# W5500_HR911105A.net
KiCad netlist of a schematic drawn in Altium Designer
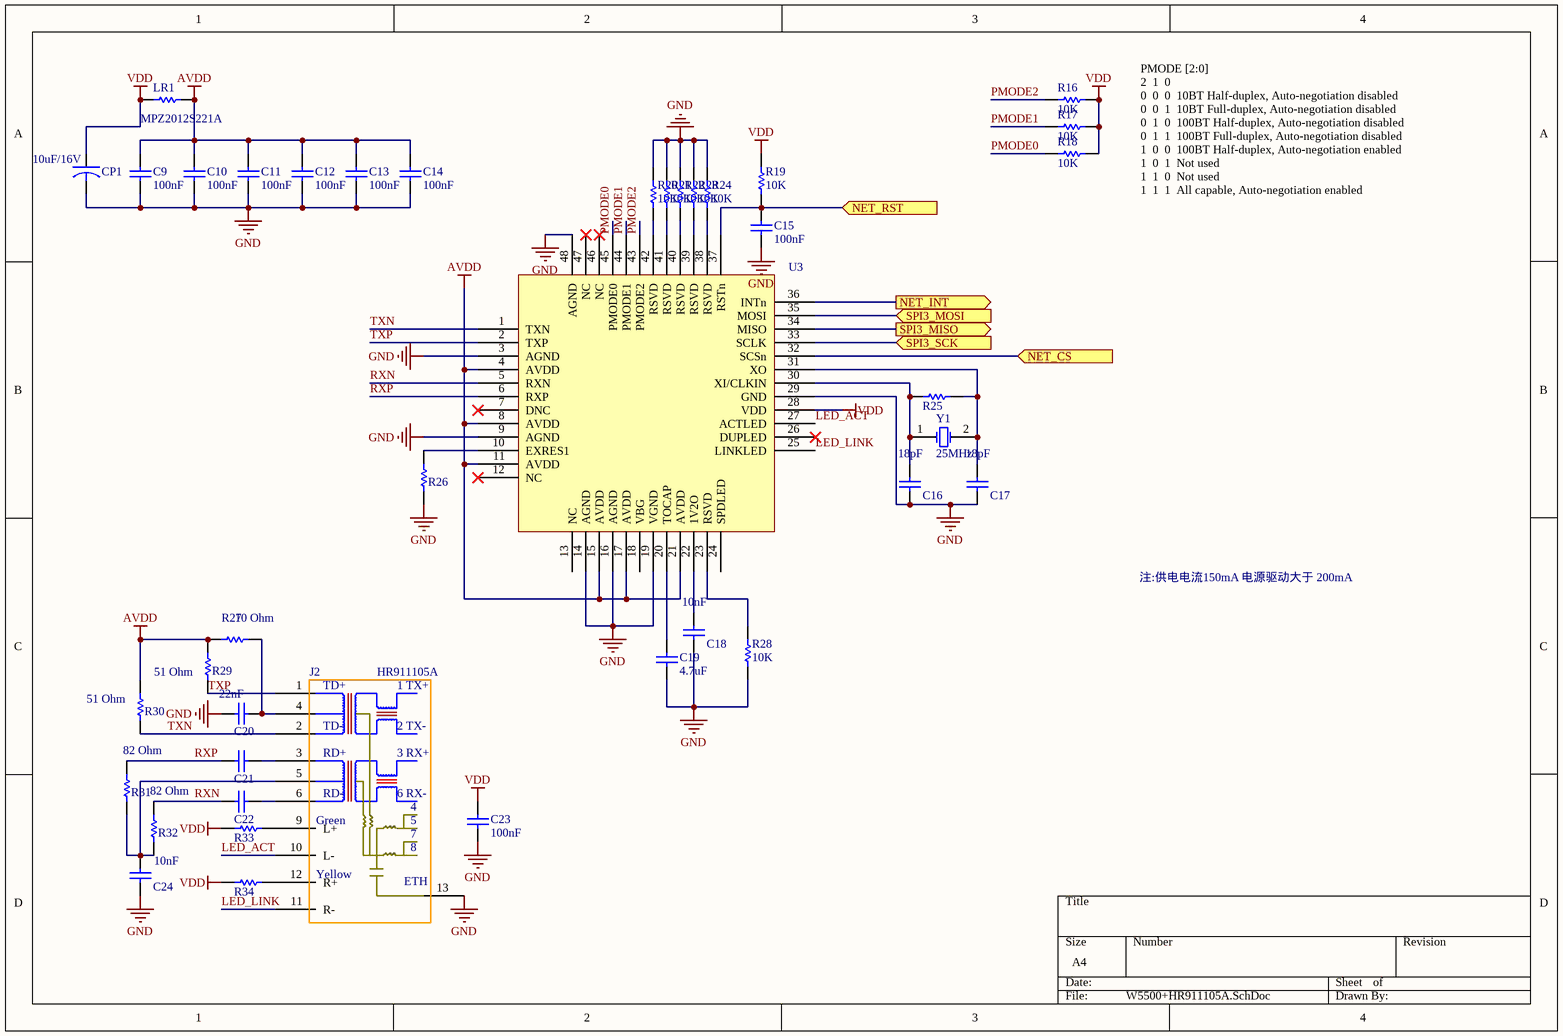
[diagram p0: W5500+HR911105A.SchDoc]

(export (version "E")
  (design (tool "Eeschema 10.0.6"))
  (components
    (comp (ref "C9")
      (value "100nF")
      (footprint "2012[0805]06CD")
      (description "CAP 100nF 50V ±5% 0805 (2012 Metric) Thickness 1mm SMD")
      (fields (field (name "TOLERANCE") "±5%") (field (name "Comment") "CAP 100nF 50V 0805(2012)"))
      (libsource (lib "Altium Content Vault") (part "CMP-1036-04418-1"))
    )
    (comp (ref "C10")
      (value "100nF")
      (footprint "2012[0805]06CD")
      (description "CAP 100nF 50V ±5% 0805 (2012 Metric) Thickness 1mm SMD")
      (fields (field (name "TOLERANCE") "±5%") (field (name "Comment") "CAP 100nF 50V 0805(2012)"))
      (libsource (lib "Altium Content Vault") (part "CMP-1036-04418-1"))
    )
    (comp (ref "C11")
      (value "100nF")
      (footprint "2012[0805]06CD")
      (description "CAP 100nF 50V ±5% 0805 (2012 Metric) Thickness 1mm SMD")
      (fields (field (name "TOLERANCE") "±5%") (field (name "Comment") "CAP 100nF 50V 0805(2012)"))
      (libsource (lib "Altium Content Vault") (part "CMP-1036-04418-1"))
    )
    (comp (ref "C12")
      (value "100nF")
      (footprint "2012[0805]06CD")
      (description "CAP 100nF 50V ±5% 0805 (2012 Metric) Thickness 1mm SMD")
      (fields (field (name "TOLERANCE") "±5%") (field (name "Comment") "CAP 100nF 50V 0805(2012)"))
      (libsource (lib "Altium Content Vault") (part "CMP-1036-04418-1"))
    )
    (comp (ref "C13")
      (value "100nF")
      (footprint "2012[0805]06CD")
      (description "CAP 100nF 50V ±5% 0805 (2012 Metric) Thickness 1mm SMD")
      (fields (field (name "TOLERANCE") "±5%") (field (name "Comment") "CAP 100nF 50V 0805(2012)"))
      (libsource (lib "Altium Content Vault") (part "CMP-1036-04418-1"))
    )
    (comp (ref "C14")
      (value "100nF")
      (footprint "2012[0805]06CD")
      (description "CAP 100nF 50V ±5% 0805 (2012 Metric) Thickness 1mm SMD")
      (fields (field (name "TOLERANCE") "±5%") (field (name "Comment") "CAP 100nF 50V 0805(2012)"))
      (libsource (lib "Altium Content Vault") (part "CMP-1036-04418-1"))
    )
    (comp (ref "C15")
      (value "100nF")
      (footprint "2012[0805]06CD")
      (description "CAP 100nF 50V ±5% 0805 (2012 Metric) Thickness 1.45mm SMD")
      (fields (field (name "TOLERANCE") "±5%") (field (name "Comment") "CAP 100nF 50V 0805(2012)"))
      (libsource (lib "Altium Content Vault") (part "CMP-1036-04417-1"))
    )
    (comp (ref "C16")
      (value "18pF")
      (footprint "2012[0805]100_L")
      (description "CAP 18pF 50V ±1% 0805 (2012 Metric) Thickness 0.75mm SMD")
      (fields (field (name "TOLERANCE") "±1%") (field (name "Comment") "CAP 18pF 50V 0805(2012)"))
      (libsource (lib "Altium Content Vault") (part "CMP-1036-01136-1"))
    )
    (comp (ref "C17")
      (value "18pF")
      (footprint "2012[0805]100_L")
      (description "CAP 18pF 50V ±1% 0805 (2012 Metric) Thickness 0.75mm SMD")
      (fields (field (name "TOLERANCE") "±1%") (field (name "Comment") "CAP 18pF 50V 0805(2012)"))
      (libsource (lib "Altium Content Vault") (part "CMP-1036-01136-1"))
    )
    (comp (ref "C18")
      (value "10nF")
      (footprint "2012[0805]100_L")
      (description "CAP 10nF 50V ±1% 0805 (2012 Metric) Thickness 1mm SMD")
      (fields (field (name "TOLERANCE") "±1%") (field (name "Comment") "CAP 10nF 50V 0805(2012)"))
      (libsource (lib "Altium Content Vault") (part "CMP-1036-03837-1"))
    )
    (comp (ref "C19")
      (value "4.7uF")
      (footprint "2012[0805]13CD")
      (description "CAP 4.7uF 50V ±10% 0805 (2012 Metric) Thickness 1.45mm SMD")
      (fields (field (name "TOLERANCE") "±10%") (field (name "Comment") "CAP 4.7uF 50V 0805(2012)"))
      (libsource (lib "Altium Content Vault") (part "CMP-1036-04900-1"))
    )
    (comp (ref "C20")
      (value "22nF")
      (footprint "2012[0805]100_L")
      (description "CAP 22nF 50V ±5% 0805 (2012 Metric) Thickness 1.2mm SMD")
      (fields (field (name "TOLERANCE") "±5%") (field (name "Comment") "CAP 22nF 50V 0805(2012)"))
      (libsource (lib "Altium Content Vault") (part "CMP-1036-04061-1"))
    )
    (comp (ref "C21")
      (value "CAP 6.8nF 50V 0805(2012)")
      (footprint "2012[0805]100_L")
      (description "CAP 6.8nF 50V ±1% 0805 (2012 Metric) Thickness 1mm SMD")
      (fields (field (name "TOLERANCE") "±1%"))
      (libsource (lib "Altium Content Vault") (part "CAP"))
    )
    (comp (ref "C22")
      (value "CAP 6.8nF 50V 0805(2012)")
      (footprint "2012[0805]100_L")
      (description "CAP 6.8nF 50V ±1% 0805 (2012 Metric) Thickness 1mm SMD")
      (fields (field (name "TOLERANCE") "±1%"))
      (libsource (lib "Altium Content Vault") (part "CAP"))
    )
    (comp (ref "C23")
      (value "100nF")
      (footprint "2012[0805]06CD")
      (description "CAP 100nF 50V ±5% 0805 (2012 Metric) Thickness 1mm SMD")
      (fields (field (name "TOLERANCE") "±5%") (field (name "Comment") "CAP 100nF 50V 0805(2012)"))
      (libsource (lib "Altium Content Vault") (part "CMP-1036-04418-1"))
    )
    (comp (ref "C24")
      (value "10nF")
      (footprint "2012[0805]100_L")
      (description "CAP 10nF 50V ±1% 0805 (2012 Metric) Thickness 1mm SMD")
      (fields (field (name "TOLERANCE") "±1%") (field (name "Comment") "CAP 10nF 50V 0805(2012)"))
      (libsource (lib "Altium Content Vault") (part "CMP-1036-03837-1"))
    )
    (comp (ref "CP1")
      (value "10uF/16V")
      (footprint "3216[1206]CB")
      (description "钽质电容器-固体SMD 16volts 10uF 10%")
      (fields (field (name "MANUFACTURER") "AVX") (field (name "MANUFACTURER PART NUMBER") "TAJA106K016RNJ"))
      (libsource (lib "*") (part "CAPACITOR"))
    )
    (comp (ref "J2") (value "HR911105A") (footprint "HR911105A") (libsource (lib "*") (part "HR911102")))
    (comp (ref "LR1")
      (value "MPZ2012S221A")
      (footprint "2012[0805]RL")
      (description "电磁干扰滤波珠子、扼流圈和阵列 Ferrite Chip Beads")
      (fields (field (name "MANUFACTURER") "TDK"))
      (libsource (lib "Miscellaneous Devices") (part "Res Semi"))
    )
    (comp (ref "R16")
      (value "10K")
      (footprint "2012[0805]R")
      (description "10K 0.125W 1% 0805 (2012 Metric)  SMD")
      (fields (field (name "TOLERANCE") "1 %") (field (name "POWER") "0.125 W"))
      (libsource (lib "Altium Content Vault") (part "CMP-1013-00623-1"))
    )
    (comp (ref "R17")
      (value "10K")
      (footprint "2012[0805]R")
      (description "10K 0.125W 1% 0805 (2012 Metric)  SMD")
      (fields (field (name "TOLERANCE") "1 %") (field (name "POWER") "0.125 W"))
      (libsource (lib "Altium Content Vault") (part "CMP-1013-00623-1"))
    )
    (comp (ref "R18")
      (value "10K")
      (footprint "2012[0805]R")
      (description "10K 0.125W 1% 0805 (2012 Metric)  SMD")
      (fields (field (name "TOLERANCE") "1 %") (field (name "POWER") "0.125 W"))
      (libsource (lib "Altium Content Vault") (part "CMP-1013-00623-1"))
    )
    (comp (ref "R19")
      (value "10K")
      (footprint "2012[0805]R")
      (description "10K 0.125W 1% 0805 (2012 Metric)  SMD")
      (fields (field (name "TOLERANCE") "1 %") (field (name "POWER") "0.125 W"))
      (libsource (lib "Altium Content Vault") (part "CMP-1013-00623-1"))
    )
    (comp (ref "R20")
      (value "10K")
      (footprint "2012[0805]R")
      (description "10K 0.125W 1% 0805 (2012 Metric)  SMD")
      (fields (field (name "TOLERANCE") "1 %") (field (name "POWER") "0.125 W"))
      (libsource (lib "Altium Content Vault") (part "CMP-1013-00623-1"))
    )
    (comp (ref "R21")
      (value "10K")
      (footprint "2012[0805]R")
      (description "10K 0.125W 1% 0805 (2012 Metric)  SMD")
      (fields (field (name "TOLERANCE") "1 %") (field (name "POWER") "0.125 W"))
      (libsource (lib "Altium Content Vault") (part "CMP-1013-00623-1"))
    )
    (comp (ref "R22")
      (value "10K")
      (footprint "2012[0805]R")
      (description "10K 0.125W 1% 0805 (2012 Metric)  SMD")
      (fields (field (name "TOLERANCE") "1 %") (field (name "POWER") "0.125 W"))
      (libsource (lib "Altium Content Vault") (part "CMP-1013-00623-1"))
    )
    (comp (ref "R23")
      (value "10K")
      (footprint "2012[0805]R")
      (description "10K 0.125W 1% 0805 (2012 Metric)  SMD")
      (fields (field (name "TOLERANCE") "1 %") (field (name "POWER") "0.125 W"))
      (libsource (lib "Altium Content Vault") (part "CMP-1013-00623-1"))
    )
    (comp (ref "R24")
      (value "10K")
      (footprint "2012[0805]R")
      (description "10K 0.125W 1% 0805 (2012 Metric)  SMD")
      (fields (field (name "TOLERANCE") "1 %") (field (name "POWER") "0.125 W"))
      (libsource (lib "Altium Content Vault") (part "CMP-1013-00623-1"))
    )
    (comp (ref "R25")
      (value "1M 1% 0805(2012)")
      (footprint "2012[0805]R")
      (description "1M 0.125W 1% 0805 (2012 Metric)  SMD")
      (fields (field (name "POWER") "0.125 W") (field (name "TOLERANCE") "1 %"))
      (libsource (lib "Altium Content Vault") (part "RES"))
    )
    (comp (ref "R26")
      (value "12K4 1% 0805(2012)")
      (footprint "2012[0805]R")
      (description "12K4 0.125W 1% 0805 (2012 Metric)  SMD")
      (fields (field (name "POWER") "0.125 W") (field (name "TOLERANCE") "1 %"))
      (libsource (lib "Altium Content Vault") (part "CMP-1013-00633-1"))
    )
    (comp (ref "R27")
      (value "10 Ohm")
      (footprint "2012[0805]R")
      (description "10R 0.125W 5% 0805 (2012 Metric)  SMD")
      (fields (field (name "POWER") "0.125 W") (field (name "TOLERANCE") "5 %"))
      (libsource (lib "Altium Content Vault") (part "CMP-1013-00026-1"))
    )
    (comp (ref "R28")
      (value "10K")
      (footprint "2012[0805]R")
      (description "10K 0.125W 1% 0805 (2012 Metric)  SMD")
      (fields (field (name "TOLERANCE") "1 %") (field (name "POWER") "0.125 W"))
      (libsource (lib "Altium Content Vault") (part "CMP-1013-00623-1"))
    )
    (comp (ref "R29")
      (value "51 Ohm")
      (footprint "2012[0805]R")
      (description "51R 0.125W 5% 0805 (2012 Metric)  SMD")
      (fields (field (name "TOLERANCE") "5 %") (field (name "POWER") "0.125 W"))
      (libsource (lib "Altium Content Vault") (part "CMP-1013-00043-1"))
    )
    (comp (ref "R30")
      (value "51 Ohm")
      (footprint "2012[0805]R")
      (description "51R 0.125W 5% 0805 (2012 Metric)  SMD")
      (fields (field (name "TOLERANCE") "5 %") (field (name "POWER") "0.125 W"))
      (libsource (lib "Altium Content Vault") (part "CMP-1013-00043-1"))
    )
    (comp (ref "R31")
      (value "82 Ohm")
      (footprint "2012[0805]R")
      (description "82R 0.125W 5% 0805 (2012 Metric)  SMD")
      (fields (field (name "POWER") "0.125 W") (field (name "TOLERANCE") "5 %"))
      (libsource (lib "Altium Content Vault") (part "CMP-1013-00048-1"))
    )
    (comp (ref "R32")
      (value "82 Ohm")
      (footprint "2012[0805]R")
      (description "82R 0.125W 5% 0805 (2012 Metric)  SMD")
      (fields (field (name "POWER") "0.125 W") (field (name "TOLERANCE") "5 %"))
      (libsource (lib "Altium Content Vault") (part "CMP-1013-00048-1"))
    )
    (comp (ref "R33")
      (value "270R 5% 0805(2012)")
      (footprint "2012[0805]R")
      (description "270R 0.125W 5% 0805 (2012 Metric)  SMD")
      (fields (field (name "POWER") "0.125 W") (field (name "TOLERANCE") "5 %"))
      (libsource (lib "Altium Content Vault") (part "RES"))
    )
    (comp (ref "R34")
      (value "270R 5% 0805(2012)")
      (footprint "2012[0805]R")
      (description "270R 0.125W 5% 0805 (2012 Metric)  SMD")
      (fields (field (name "POWER") "0.125 W") (field (name "TOLERANCE") "5 %"))
      (libsource (lib "Altium Content Vault") (part "RES"))
    )
    (comp (ref "U3")
      (value "W5500")
      (footprint "LQFP48_N")
      (description "以太网")
      (libsource (lib "mylib") (part "W5500"))
    )
    (comp (ref "Y1")
      (value "25MHz")
      (footprint "XTAL_HC-49")
      (description "Crystal Oscillator")
      (fields (field (name "PUBLISHER") "Altium Limited"))
      (libsource (lib "mylib") (part "XTAL"))
    )
  )
  (nets
    (net (code "1") (name "/LED_ACT") (class "Default")
      (node (ref "J2") (pin "10") (pinfunction "L-_10") (pintype "passive"))
      (node (ref "U3") (pin "27") (pinfunction "ACTLED_27") (pintype "passive"))
    )
    (net (code "2") (name "/LED_LINK") (class "Default")
      (node (ref "J2") (pin "11") (pinfunction "R-_11") (pintype "passive"))
      (node (ref "U3") (pin "25") (pinfunction "LINKLED_25") (pintype "passive"))
    )
    (net (code "3") (name "/NET_CS") (class "Default")
      (node (ref "U3") (pin "32") (pinfunction "SCSn_32") (pintype "passive"))
    )
    (net (code "4") (name "/NET_INT") (class "Default")
      (node (ref "U3") (pin "36") (pinfunction "INTn_36") (pintype "passive"))
    )
    (net (code "5") (name "/NET_RST") (class "Default")
      (node (ref "C15") (pin "1") (pinfunction "1_1") (pintype "passive"))
      (node (ref "R19") (pin "2") (pinfunction "2_2") (pintype "passive"))
      (node (ref "U3") (pin "37") (pinfunction "RSTn_37") (pintype "passive"))
    )
    (net (code "6") (name "/PMODE0") (class "Default")
      (node (ref "R18") (pin "2") (pinfunction "2_2") (pintype "passive"))
      (node (ref "U3") (pin "45") (pinfunction "PMODE0_45") (pintype "passive"))
    )
    (net (code "7") (name "/PMODE1") (class "Default")
      (node (ref "R17") (pin "2") (pinfunction "2_2") (pintype "passive"))
      (node (ref "U3") (pin "44") (pinfunction "PMODE1_44") (pintype "passive"))
    )
    (net (code "8") (name "/PMODE2") (class "Default")
      (node (ref "R16") (pin "2") (pinfunction "2_2") (pintype "passive"))
      (node (ref "U3") (pin "43") (pinfunction "PMODE2_43") (pintype "passive"))
    )
    (net (code "9") (name "/RXN") (class "Default")
      (node (ref "C22") (pin "1") (pinfunction "1_1") (pintype "passive"))
      (node (ref "R32") (pin "2") (pinfunction "2_2") (pintype "passive"))
      (node (ref "U3") (pin "5") (pinfunction "RXN_5") (pintype "passive"))
    )
    (net (code "10") (name "/RXP") (class "Default")
      (node (ref "C21") (pin "1") (pinfunction "1_1") (pintype "passive"))
      (node (ref "R31") (pin "2") (pinfunction "2_2") (pintype "passive"))
      (node (ref "U3") (pin "6") (pinfunction "RXP_6") (pintype "passive"))
    )
    (net (code "11") (name "/SPI3_MISO") (class "Default")
      (node (ref "U3") (pin "34") (pinfunction "MISO_34") (pintype "passive"))
    )
    (net (code "12") (name "/SPI3_MOSI") (class "Default")
      (node (ref "U3") (pin "35") (pinfunction "MOSI_35") (pintype "passive"))
    )
    (net (code "13") (name "/SPI3_SCK") (class "Default")
      (node (ref "U3") (pin "33") (pinfunction "SCLK_33") (pintype "passive"))
    )
    (net (code "14") (name "/TXN") (class "Default")
      (node (ref "J2") (pin "2") (pintype "passive"))
      (node (ref "R30") (pin "1") (pinfunction "1_1") (pintype "passive"))
      (node (ref "U3") (pin "1") (pinfunction "TXN_1") (pintype "passive"))
    )
    (net (code "15") (name "/TXP") (class "Default")
      (node (ref "J2") (pin "1") (pintype "passive"))
      (node (ref "R29") (pin "1") (pinfunction "1_1") (pintype "passive"))
      (node (ref "U3") (pin "2") (pinfunction "TXP_2") (pintype "passive"))
    )
    (net (code "16") (name "AVDD") (class "Default")
      (node (ref "C10") (pin "1") (pinfunction "1_1") (pintype "passive"))
      (node (ref "C11") (pin "1") (pinfunction "1_1") (pintype "passive"))
      (node (ref "C12") (pin "1") (pinfunction "1_1") (pintype "passive"))
      (node (ref "C13") (pin "1") (pinfunction "1_1") (pintype "passive"))
      (node (ref "C14") (pin "1") (pinfunction "1_1") (pintype "passive"))
      (node (ref "C9") (pin "1") (pinfunction "1_1") (pintype "passive"))
      (node (ref "LR1") (pin "1") (pinfunction "1_1") (pintype "passive"))
      (node (ref "R27") (pin "2") (pinfunction "2_2") (pintype "passive"))
      (node (ref "R29") (pin "2") (pinfunction "2_2") (pintype "passive"))
      (node (ref "R30") (pin "2") (pinfunction "2_2") (pintype "passive"))
      (node (ref "U3") (pin "11") (pinfunction "AVDD_11") (pintype "passive"))
      (node (ref "U3") (pin "15") (pinfunction "AVDD_15") (pintype "passive"))
      (node (ref "U3") (pin "17") (pinfunction "AVDD_17") (pintype "passive"))
      (node (ref "U3") (pin "21") (pinfunction "AVDD_21") (pintype "passive"))
      (node (ref "U3") (pin "4") (pinfunction "AVDD_4") (pintype "passive"))
      (node (ref "U3") (pin "8") (pinfunction "AVDD_8") (pintype "passive"))
    )
    (net (code "17") (name "GND") (class "Default")
      (node (ref "C10") (pin "2") (pinfunction "2_2") (pintype "passive"))
      (node (ref "C11") (pin "2") (pinfunction "2_2") (pintype "passive"))
      (node (ref "C12") (pin "2") (pinfunction "2_2") (pintype "passive"))
      (node (ref "C13") (pin "2") (pinfunction "2_2") (pintype "passive"))
      (node (ref "C14") (pin "2") (pinfunction "2_2") (pintype "passive"))
      (node (ref "C15") (pin "2") (pinfunction "2_2") (pintype "passive"))
      (node (ref "C16") (pin "1") (pinfunction "1_1") (pintype "passive"))
      (node (ref "C17") (pin "1") (pinfunction "1_1") (pintype "passive"))
      (node (ref "C18") (pin "1") (pinfunction "1_1") (pintype "passive"))
      (node (ref "C19") (pin "2") (pinfunction "2_2") (pintype "passive"))
      (node (ref "C20") (pin "1") (pinfunction "1_1") (pintype "passive"))
      (node (ref "C23") (pin "2") (pinfunction "2_2") (pintype "passive"))
      (node (ref "C24") (pin "1") (pinfunction "1_1") (pintype "passive"))
      (node (ref "C9") (pin "2") (pinfunction "2_2") (pintype "passive"))
      (node (ref "CP1") (pin "2") (pinfunction "2_2") (pintype "passive"))
      (node (ref "J2") (pin "13") (pintype "passive"))
      (node (ref "R20") (pin "1") (pinfunction "1_1") (pintype "passive"))
      (node (ref "R21") (pin "1") (pinfunction "1_1") (pintype "passive"))
      (node (ref "R22") (pin "1") (pinfunction "1_1") (pintype "passive"))
      (node (ref "R23") (pin "1") (pinfunction "1_1") (pintype "passive"))
      (node (ref "R24") (pin "1") (pinfunction "1_1") (pintype "passive"))
      (node (ref "R26") (pin "1") (pinfunction "1_1") (pintype "passive"))
      (node (ref "R28") (pin "2") (pinfunction "2_2") (pintype "passive"))
      (node (ref "U3") (pin "14") (pinfunction "AGND_14") (pintype "passive"))
      (node (ref "U3") (pin "16") (pinfunction "AGND_16") (pintype "passive"))
      (node (ref "U3") (pin "19") (pinfunction "VGND_19") (pintype "passive"))
      (node (ref "U3") (pin "29") (pinfunction "GND_29") (pintype "passive"))
      (node (ref "U3") (pin "3") (pinfunction "AGND_3") (pintype "passive"))
      (node (ref "U3") (pin "48") (pinfunction "AGND_48") (pintype "passive"))
      (node (ref "U3") (pin "9") (pinfunction "AGND_9") (pintype "passive"))
    )
    (net (code "18") (name "Net-(C20-Pad2)") (class "Default")
      (node (ref "C20") (pin "2") (pinfunction "2_2") (pintype "passive"))
      (node (ref "J2") (pin "4") (pintype "passive"))
      (node (ref "R27") (pin "1") (pinfunction "1_1") (pintype "passive"))
    )
    (net (code "19") (name "Net-(C21-Pad2)") (class "Default")
      (node (ref "C21") (pin "2") (pinfunction "2_2") (pintype "passive"))
      (node (ref "J2") (pin "3") (pintype "passive"))
    )
    (net (code "20") (name "Net-(C22-Pad2)") (class "Default")
      (node (ref "C22") (pin "2") (pinfunction "2_2") (pintype "passive"))
      (node (ref "J2") (pin "6") (pintype "passive"))
    )
    (net (code "21") (name "Net-(C24-Pad2)") (class "Default")
      (node (ref "C24") (pin "2") (pinfunction "2_2") (pintype "passive"))
      (node (ref "J2") (pin "5") (pintype "passive"))
      (node (ref "R31") (pin "1") (pinfunction "1_1") (pintype "passive"))
      (node (ref "R32") (pin "1") (pinfunction "1_1") (pintype "passive"))
    )
    (net (code "22") (name "Net-(J2-L+)") (class "Default")
      (node (ref "J2") (pin "9") (pinfunction "L+_9") (pintype "passive"))
      (node (ref "R33") (pin "2") (pinfunction "2_2") (pintype "passive"))
    )
    (net (code "23") (name "Net-(J2-R+)") (class "Default")
      (node (ref "J2") (pin "12") (pinfunction "R+_12") (pintype "passive"))
      (node (ref "R34") (pin "2") (pinfunction "2_2") (pintype "passive"))
    )
    (net (code "24") (name "Net-(R20-Pad2)") (class "Default")
      (node (ref "R20") (pin "2") (pinfunction "2_2") (pintype "passive"))
      (node (ref "U3") (pin "42") (pinfunction "RSVD_42") (pintype "passive"))
    )
    (net (code "25") (name "Net-(R21-Pad2)") (class "Default")
      (node (ref "R21") (pin "2") (pinfunction "2_2") (pintype "passive"))
      (node (ref "U3") (pin "41") (pinfunction "RSVD_41") (pintype "passive"))
    )
    (net (code "26") (name "Net-(R22-Pad2)") (class "Default")
      (node (ref "R22") (pin "2") (pinfunction "2_2") (pintype "passive"))
      (node (ref "U3") (pin "40") (pinfunction "RSVD_40") (pintype "passive"))
    )
    (net (code "27") (name "Net-(R23-Pad2)") (class "Default")
      (node (ref "R23") (pin "2") (pinfunction "2_2") (pintype "passive"))
      (node (ref "U3") (pin "39") (pinfunction "RSVD_39") (pintype "passive"))
    )
    (net (code "28") (name "Net-(R24-Pad2)") (class "Default")
      (node (ref "R24") (pin "2") (pinfunction "2_2") (pintype "passive"))
      (node (ref "U3") (pin "38") (pinfunction "RSVD_38") (pintype "passive"))
    )
    (net (code "29") (name "Net-(R28-Pad1)") (class "Default")
      (node (ref "R28") (pin "1") (pinfunction "1_1") (pintype "passive"))
      (node (ref "U3") (pin "23") (pinfunction "RSVD_23") (pintype "passive"))
    )
    (net (code "30") (name "Net-(U3-1V2O)") (class "Default")
      (node (ref "C18") (pin "2") (pinfunction "2_2") (pintype "passive"))
      (node (ref "U3") (pin "22") (pinfunction "1V2O_22") (pintype "passive"))
    )
    (net (code "31") (name "Net-(U3-EXRES1)") (class "Default")
      (node (ref "R26") (pin "2") (pinfunction "2_2") (pintype "passive"))
      (node (ref "U3") (pin "10") (pinfunction "EXRES1_10") (pintype "passive"))
    )
    (net (code "32") (name "Net-(U3-TOCAP)") (class "Default")
      (node (ref "C19") (pin "1") (pinfunction "1_1") (pintype "passive"))
      (node (ref "U3") (pin "20") (pinfunction "TOCAP_20") (pintype "passive"))
    )
    (net (code "33") (name "Net-(U3-XI{slash}CLKIN)") (class "Default")
      (node (ref "C16") (pin "2") (pinfunction "2_2") (pintype "passive"))
      (node (ref "R25") (pin "1") (pinfunction "1_1") (pintype "passive"))
      (node (ref "U3") (pin "30") (pinfunction "XI/CLKIN_30") (pintype "passive"))
      (node (ref "Y1") (pin "1") (pinfunction "OSC1_1") (pintype "passive"))
    )
    (net (code "34") (name "Net-(U3-XO)") (class "Default")
      (node (ref "C17") (pin "2") (pinfunction "2_2") (pintype "passive"))
      (node (ref "R25") (pin "2") (pinfunction "2_2") (pintype "passive"))
      (node (ref "U3") (pin "31") (pinfunction "XO_31") (pintype "passive"))
      (node (ref "Y1") (pin "2") (pinfunction "OSC2_2") (pintype "passive"))
    )
    (net (code "35") (name "VDD") (class "Default")
      (node (ref "C23") (pin "1") (pinfunction "1_1") (pintype "passive"))
      (node (ref "CP1") (pin "1") (pinfunction "1_1") (pintype "passive"))
      (node (ref "LR1") (pin "2") (pinfunction "2_2") (pintype "passive"))
      (node (ref "R16") (pin "1") (pinfunction "1_1") (pintype "passive"))
      (node (ref "R17") (pin "1") (pinfunction "1_1") (pintype "passive"))
      (node (ref "R18") (pin "1") (pinfunction "1_1") (pintype "passive"))
      (node (ref "R19") (pin "1") (pinfunction "1_1") (pintype "passive"))
      (node (ref "R33") (pin "1") (pinfunction "1_1") (pintype "passive"))
      (node (ref "R34") (pin "1") (pinfunction "1_1") (pintype "passive"))
      (node (ref "U3") (pin "28") (pinfunction "VDD_28") (pintype "passive"))
    )
    (net (code "36") (name "unconnected-(U3-DNC-Pad7)") (class "Default")
      (node (ref "U3") (pin "7") (pinfunction "DNC_7") (pintype "passive+no_connect"))
    )
    (net (code "37") (name "unconnected-(U3-DUPLED-Pad26)") (class "Default")
      (node (ref "U3") (pin "26") (pinfunction "DUPLED_26") (pintype "passive+no_connect"))
    )
    (net (code "38") (name "unconnected-(U3-NC-Pad12)") (class "Default")
      (node (ref "U3") (pin "12") (pinfunction "NC_12") (pintype "passive+no_connect"))
    )
    (net (code "39") (name "unconnected-(U3-NC-Pad13)") (class "Default")
      (node (ref "U3") (pin "13") (pinfunction "NC_13") (pintype "passive"))
    )
    (net (code "40") (name "unconnected-(U3-NC-Pad46)") (class "Default")
      (node (ref "U3") (pin "46") (pinfunction "NC_46") (pintype "passive+no_connect"))
    )
    (net (code "41") (name "unconnected-(U3-NC-Pad47)") (class "Default")
      (node (ref "U3") (pin "47") (pinfunction "NC_47") (pintype "passive+no_connect"))
    )
    (net (code "42") (name "unconnected-(U3-SPDLED-Pad24)") (class "Default")
      (node (ref "U3") (pin "24") (pinfunction "SPDLED_24") (pintype "passive"))
    )
    (net (code "43") (name "unconnected-(U3-VBG-Pad18)") (class "Default")
      (node (ref "U3") (pin "18") (pinfunction "VBG_18") (pintype "passive"))
    )
  )
)
